# V15_USB_isolator.net
KiCad netlist of a schematic drawn in EAGLE
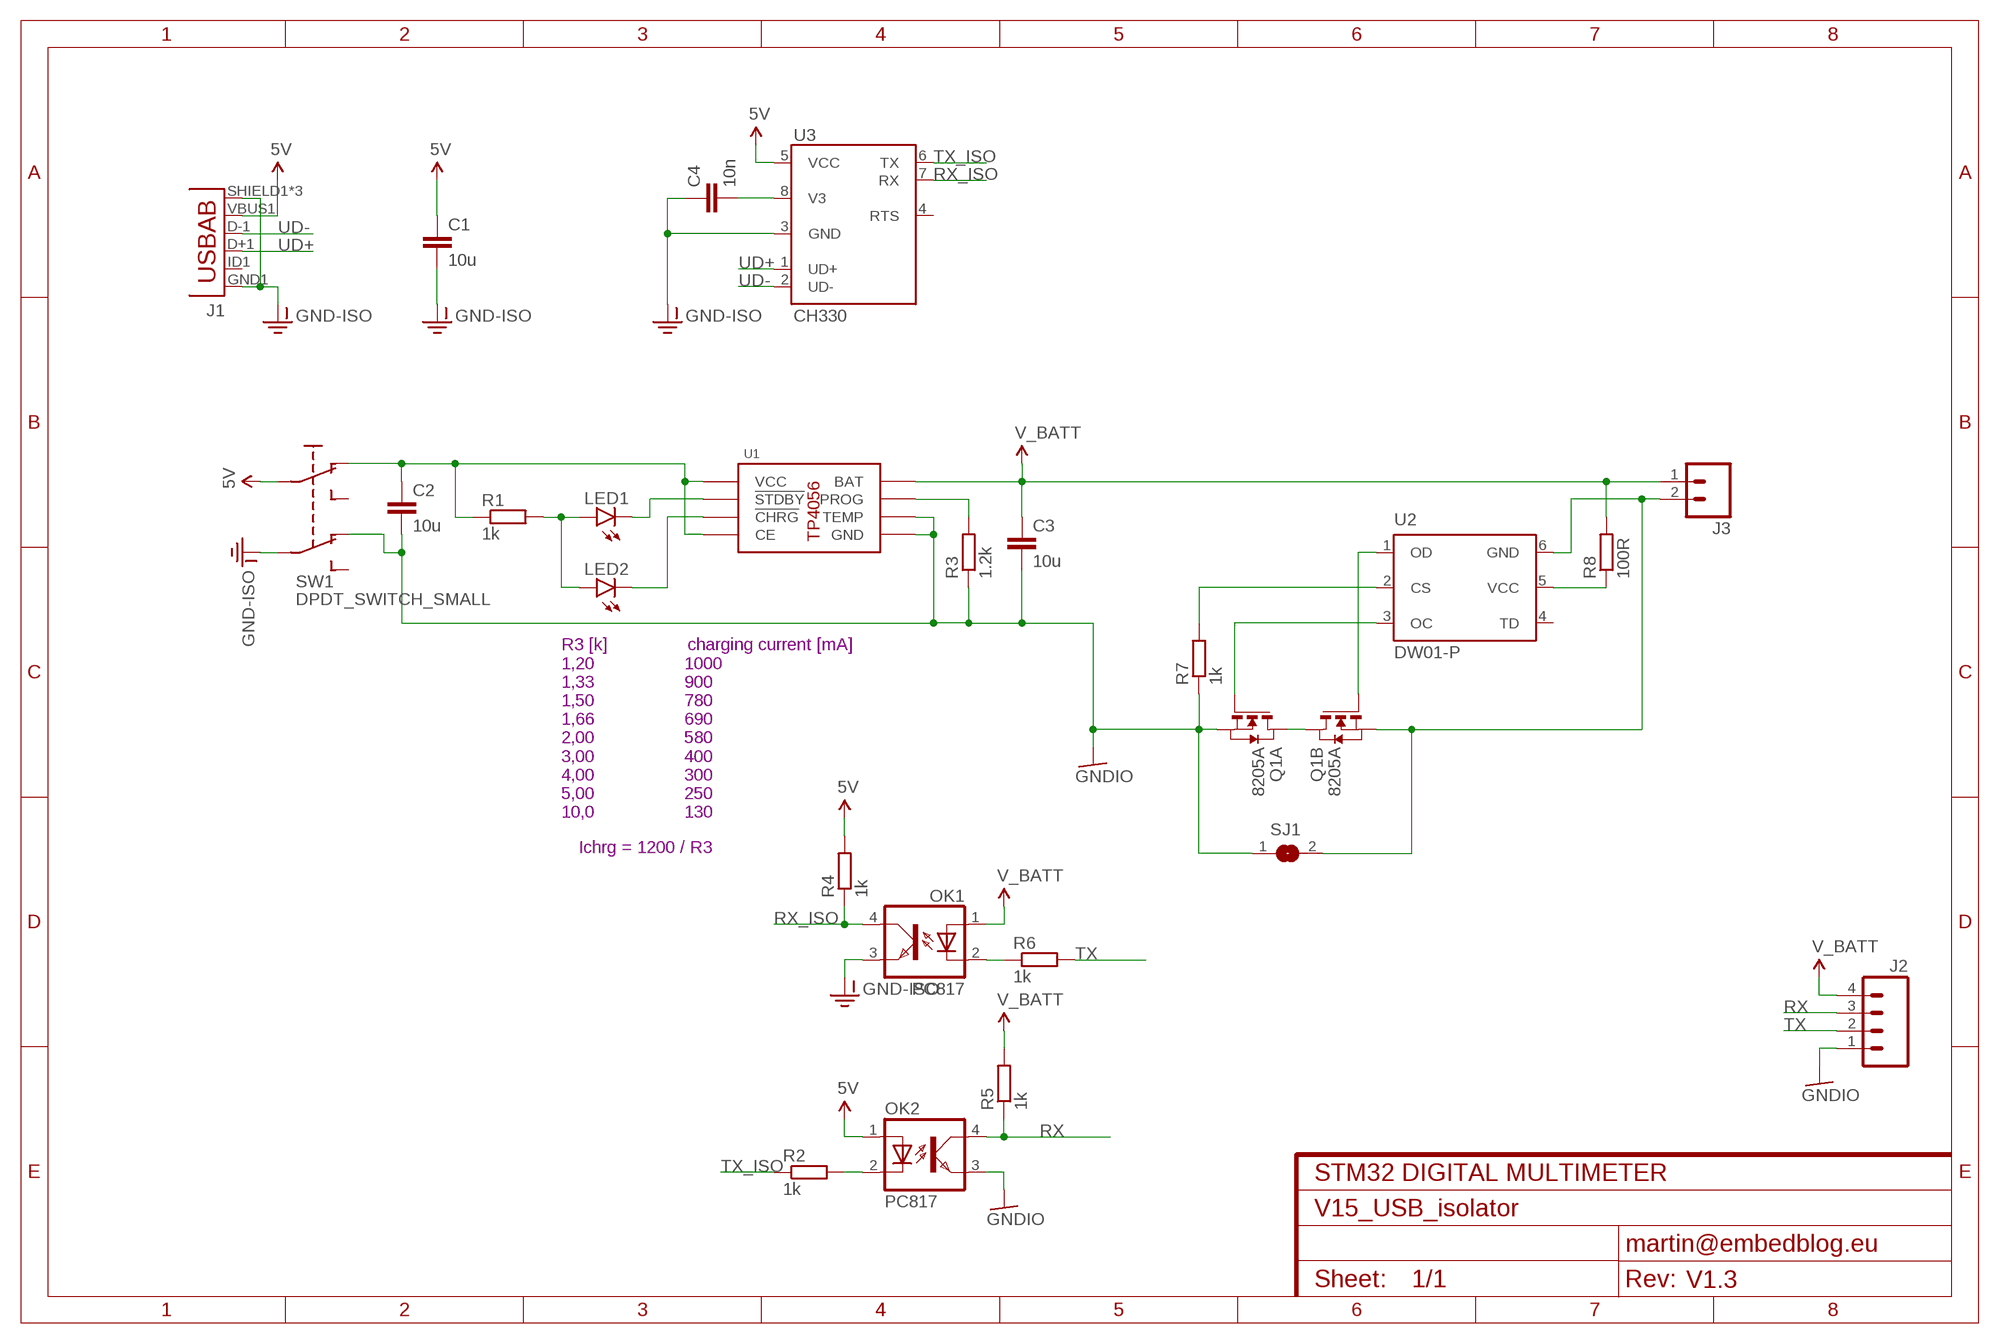
[diagram p0: schematic, sheet 1]

(export (version "E")
  (design (tool "Eeschema 10.0.6"))
  (components
    (comp (ref "C1")
      (value "10u")
      (footprint "eagle-import:C1206")
      (libsource (lib "eagle-import") (part "C-EUC1206"))
    )
    (comp (ref "C2")
      (value "10u")
      (footprint "eagle-import:C1206")
      (libsource (lib "eagle-import") (part "C-EUC1206"))
    )
    (comp (ref "C3")
      (value "10u")
      (footprint "eagle-import:C1206")
      (libsource (lib "eagle-import") (part "C-EUC1206"))
    )
    (comp (ref "C4")
      (value "10n")
      (footprint "eagle-import:C1206")
      (libsource (lib "eagle-import") (part "C-EUC1206"))
    )
    (comp (ref "J1")
      (value "USB-ABCONN-11794")
      (footprint "eagle-import:USB-AB-MICRO-SMD_V03")
      (libsource (lib "eagle-import") (part "USB-ABCONN-11794"))
    )
    (comp (ref "J2")
      (value "M04PTH")
      (footprint "eagle-import:1X04@1")
      (libsource (lib "eagle-import") (part "M04PTH"))
    )
    (comp (ref "J3")
      (value "M02PTH3")
      (footprint "eagle-import:1X02_LONGPADS")
      (libsource (lib "eagle-import") (part "M02PTH3"))
    )
    (comp (ref "LED1")
      (value "LED1206-BOTTOM")
      (footprint "eagle-import:LED-1206-BOTTOM")
      (libsource (lib "eagle-import") (part "LED1206-BOTTOM"))
    )
    (comp (ref "LED2")
      (value "LED1206-BOTTOM")
      (footprint "eagle-import:LED-1206-BOTTOM")
      (libsource (lib "eagle-import") (part "LED1206-BOTTOM"))
    )
    (comp (ref "OK1")
      (value "PC817")
      (footprint "eagle-import:DIL04")
      (fields (field (name "MPN") "PC817X4J000F"))
      (libsource (lib "eagle-import") (part "PC817"))
    )
    (comp (ref "OK2")
      (value "PC817")
      (footprint "eagle-import:DIL04")
      (fields (field (name "MPN") "PC817X4J000F"))
      (libsource (lib "eagle-import") (part "PC817"))
    )
    (comp (ref "Q1")
      (value "8205A")
      (footprint "eagle-import:TSSOP8")
      (libsource (lib "eagle-import") (part "8205A"))
    )
    (comp (ref "R1")
      (value "1k")
      (footprint "eagle-import:R1206")
      (libsource (lib "eagle-import") (part "R-EU_R1206"))
    )
    (comp (ref "R2")
      (value "1k")
      (footprint "eagle-import:R1206")
      (libsource (lib "eagle-import") (part "R-EU_R1206"))
    )
    (comp (ref "R3")
      (value "1.2k")
      (footprint "eagle-import:R1206")
      (libsource (lib "eagle-import") (part "R-EU_R1206"))
    )
    (comp (ref "R4")
      (value "1k")
      (footprint "eagle-import:R1206")
      (libsource (lib "eagle-import") (part "R-EU_R1206"))
    )
    (comp (ref "R5")
      (value "1k")
      (footprint "eagle-import:R1206")
      (libsource (lib "eagle-import") (part "R-EU_R1206"))
    )
    (comp (ref "R6")
      (value "1k")
      (footprint "eagle-import:R1206")
      (libsource (lib "eagle-import") (part "R-EU_R1206"))
    )
    (comp (ref "R7")
      (value "1k")
      (footprint "eagle-import:R1206")
      (libsource (lib "eagle-import") (part "R-EU_R1206"))
    )
    (comp (ref "R8")
      (value "100R")
      (footprint "eagle-import:R1206")
      (libsource (lib "eagle-import") (part "R-EU_R1206"))
    )
    (comp (ref "SJ1") (value "SJ") (footprint "eagle-import:SJ") (libsource (lib "eagle-import") (part "SJ")))
    (comp (ref "SW1")
      (value "DPDT_SWITCH_SMALL")
      (footprint "eagle-import:DPDT_SMALL")
      (libsource (lib "eagle-import") (part "DPDT_SWITCH_SMALL"))
    )
    (comp (ref "U1")
      (value "TP4056")
      (footprint "eagle-import:SOP8")
      (libsource (lib "eagle-import") (part "TP4056"))
    )
    (comp (ref "U2")
      (value "DW01-P")
      (footprint "eagle-import:SOT23-6L")
      (libsource (lib "eagle-import") (part "DW01-P"))
    )
    (comp (ref "U3")
      (value "CH330")
      (footprint "eagle-import:SO08")
      (libsource (lib "eagle-import") (part "CH330"))
    )
  )
  (nets
    (net (code "1") (name "/RX") (class "Default")
      (node (ref "J2") (pin "3") (pinfunction "3_3") (pintype "passive"))
      (node (ref "OK2") (pin "4") (pinfunction "COL_4") (pintype "passive"))
      (node (ref "R5") (pin "1") (pinfunction "1_1") (pintype "passive"))
    )
    (net (code "2") (name "/RX_ISO") (class "Default")
      (node (ref "OK1") (pin "4") (pinfunction "COL_4") (pintype "passive"))
      (node (ref "R4") (pin "1") (pinfunction "1_1") (pintype "passive"))
      (node (ref "U3") (pin "7") (pinfunction "RX_7") (pintype "bidirectional"))
    )
    (net (code "3") (name "/TX") (class "Default")
      (node (ref "J2") (pin "2") (pinfunction "2_2") (pintype "passive"))
      (node (ref "R6") (pin "2") (pinfunction "2_2") (pintype "passive"))
    )
    (net (code "4") (name "/TX_ISO") (class "Default")
      (node (ref "R2") (pin "1") (pinfunction "1_1") (pintype "passive"))
      (node (ref "U3") (pin "6") (pinfunction "TX_6") (pintype "bidirectional"))
    )
    (net (code "5") (name "/UD+") (class "Default")
      (node (ref "J1") (pin "D+1") (pinfunction "D+_D+1") (pintype "bidirectional"))
      (node (ref "U3") (pin "1") (pinfunction "UD+_1") (pintype "bidirectional"))
    )
    (net (code "6") (name "/UD-") (class "Default")
      (node (ref "J1") (pin "D-1") (pinfunction "D-_D-1") (pintype "bidirectional"))
      (node (ref "U3") (pin "2") (pinfunction "UD-_2") (pintype "bidirectional"))
    )
    (net (code "7") (name "5V") (class "Default")
      (node (ref "C1") (pin "1") (pinfunction "1_1") (pintype "passive"))
      (node (ref "J1") (pin "VBUS1") (pinfunction "VBUS_VBUS1") (pintype "bidirectional"))
      (node (ref "OK2") (pin "1") (pinfunction "A_1") (pintype "passive"))
      (node (ref "R4") (pin "2") (pinfunction "2_2") (pintype "passive"))
      (node (ref "SW1") (pin "P$2") (pinfunction "I1_P$2") (pintype "passive"))
      (node (ref "U3") (pin "5") (pinfunction "VCC_5") (pintype "bidirectional"))
    )
    (net (code "8") (name "GND-ISO") (class "Default")
      (node (ref "C1") (pin "2") (pinfunction "2_2") (pintype "passive"))
      (node (ref "C4") (pin "1") (pinfunction "1_1") (pintype "passive"))
      (node (ref "J1") (pin "GND1") (pinfunction "GND_GND1") (pintype "bidirectional"))
      (node (ref "J1") (pin "SHIELD1") (pinfunction "SHIELD_SHIELD1") (pintype "bidirectional"))
      (node (ref "J1") (pin "SHIELD2") (pinfunction "SHIELD_SHIELD2") (pintype "bidirectional"))
      (node (ref "J1") (pin "SHIELD3") (pinfunction "SHIELD_SHIELD3") (pintype "bidirectional"))
      (node (ref "OK1") (pin "3") (pinfunction "EMIT_3") (pintype "passive"))
      (node (ref "SW1") (pin "P$5") (pinfunction "I2_P$5") (pintype "passive"))
      (node (ref "U3") (pin "3") (pinfunction "GND_3") (pintype "bidirectional"))
    )
    (net (code "9") (name "GNDIO") (class "Default")
      (node (ref "C2") (pin "2") (pinfunction "2_2") (pintype "passive"))
      (node (ref "C3") (pin "2") (pinfunction "2_2") (pintype "passive"))
      (node (ref "J2") (pin "1") (pinfunction "1_1") (pintype "passive"))
      (node (ref "OK2") (pin "3") (pinfunction "EMIT_3") (pintype "passive"))
      (node (ref "Q1") (pin "2") (pinfunction "S_2") (pintype "passive"))
      (node (ref "Q1") (pin "3") (pinfunction "S_3") (pintype "passive"))
      (node (ref "R3") (pin "1") (pinfunction "1_1") (pintype "passive"))
      (node (ref "R7") (pin "1") (pinfunction "1_1") (pintype "passive"))
      (node (ref "SJ1") (pin "1") (pinfunction "1_1") (pintype "passive"))
      (node (ref "SW1") (pin "P$6") (pinfunction "NC2_P$6") (pintype "passive"))
      (node (ref "U1") (pin "1") (pinfunction "TEMP_1") (pintype "bidirectional"))
      (node (ref "U1") (pin "3") (pinfunction "GND_3") (pintype "bidirectional"))
    )
    (net (code "10") (name "Net-(LED1-PadA)") (class "Default")
      (node (ref "LED1") (pin "A") (pinfunction "A_A") (pintype "passive"))
      (node (ref "LED2") (pin "A") (pinfunction "A_A") (pintype "passive"))
      (node (ref "R1") (pin "2") (pinfunction "2_2") (pintype "passive"))
    )
    (net (code "11") (name "Net-(OK1-C)") (class "Default")
      (node (ref "OK1") (pin "2") (pinfunction "C_2") (pintype "passive"))
      (node (ref "R6") (pin "1") (pinfunction "1_1") (pintype "passive"))
    )
    (net (code "12") (name "Net-(OK2-C)") (class "Default")
      (node (ref "OK2") (pin "2") (pinfunction "C_2") (pintype "passive"))
      (node (ref "R2") (pin "2") (pinfunction "2_2") (pintype "passive"))
    )
    (net (code "13") (name "Net-(Q1A-D)") (class "Default")
      (node (ref "Q1") (pin "1") (pinfunction "D_1") (pintype "passive"))
      (node (ref "Q1") (pin "8") (pinfunction "D_8") (pintype "passive"))
    )
    (net (code "14") (name "Net-(Q1A-G)") (class "Default")
      (node (ref "Q1") (pin "4") (pinfunction "G_4") (pintype "passive"))
      (node (ref "U2") (pin "3") (pinfunction "OC_3") (pintype "power_in"))
    )
    (net (code "15") (name "Net-(Q1B-G)") (class "Default")
      (node (ref "Q1") (pin "5") (pinfunction "G_5") (pintype "passive"))
      (node (ref "U2") (pin "1") (pinfunction "OD_1") (pintype "power_in"))
    )
    (net (code "16") (name "Net-(SW1-NC1)") (class "Default")
      (node (ref "C2") (pin "1") (pinfunction "1_1") (pintype "passive"))
      (node (ref "R1") (pin "1") (pinfunction "1_1") (pintype "passive"))
      (node (ref "SW1") (pin "P$1") (pinfunction "NC1_P$1") (pintype "passive"))
      (node (ref "U1") (pin "4") (pinfunction "VCC_4") (pintype "bidirectional"))
      (node (ref "U1") (pin "8") (pinfunction "CE_8") (pintype "bidirectional"))
    )
    (net (code "17") (name "Net-(U1-PROG)") (class "Default")
      (node (ref "R3") (pin "2") (pinfunction "2_2") (pintype "passive"))
      (node (ref "U1") (pin "2") (pinfunction "PROG_2") (pintype "bidirectional"))
    )
    (net (code "18") (name "Net-(U1-~{CHRG})") (class "Default")
      (node (ref "LED2") (pin "C") (pinfunction "C_C") (pintype "passive"))
      (node (ref "U1") (pin "7") (pinfunction "~{CHRG}_7") (pintype "bidirectional"))
    )
    (net (code "19") (name "Net-(U1-~{STDBY})") (class "Default")
      (node (ref "LED1") (pin "C") (pinfunction "C_C") (pintype "passive"))
      (node (ref "U1") (pin "6") (pinfunction "~{STDBY}_6") (pintype "bidirectional"))
    )
    (net (code "20") (name "Net-(U2-CS)") (class "Default")
      (node (ref "R7") (pin "2") (pinfunction "2_2") (pintype "passive"))
      (node (ref "U2") (pin "2") (pinfunction "CS_2") (pintype "input"))
    )
    (net (code "21") (name "Net-(U2-GND)") (class "Default")
      (node (ref "J3") (pin "2") (pinfunction "2_2") (pintype "passive"))
      (node (ref "Q1") (pin "6") (pinfunction "S_6") (pintype "passive"))
      (node (ref "Q1") (pin "7") (pinfunction "S_7") (pintype "passive"))
      (node (ref "SJ1") (pin "2") (pinfunction "2_2") (pintype "passive"))
      (node (ref "U2") (pin "6") (pinfunction "GND_6") (pintype "output"))
    )
    (net (code "22") (name "Net-(U2-VCC)") (class "Default")
      (node (ref "R8") (pin "1") (pinfunction "1_1") (pintype "passive"))
      (node (ref "U2") (pin "5") (pinfunction "VCC_5") (pintype "input"))
    )
    (net (code "23") (name "Net-(U3-V3)") (class "Default")
      (node (ref "C4") (pin "2") (pinfunction "2_2") (pintype "passive"))
      (node (ref "U3") (pin "8") (pinfunction "V3_8") (pintype "bidirectional"))
    )
    (net (code "24") (name "V_BATT") (class "Default")
      (node (ref "C3") (pin "1") (pinfunction "1_1") (pintype "passive"))
      (node (ref "J2") (pin "4") (pinfunction "4_4") (pintype "passive"))
      (node (ref "J3") (pin "1") (pinfunction "1_1") (pintype "passive"))
      (node (ref "OK1") (pin "1") (pinfunction "A_1") (pintype "passive"))
      (node (ref "R5") (pin "2") (pinfunction "2_2") (pintype "passive"))
      (node (ref "R8") (pin "2") (pinfunction "2_2") (pintype "passive"))
      (node (ref "U1") (pin "5") (pinfunction "BAT_5") (pintype "bidirectional"))
    )
    (net (code "25") (name "unconnected-(J1-USBID-PadID1)") (class "Default")
      (node (ref "J1") (pin "ID1") (pinfunction "USBID_ID1") (pintype "bidirectional"))
    )
    (net (code "26") (name "unconnected-(SW1-NO1-PadP$3)") (class "Default")
      (node (ref "SW1") (pin "P$3") (pinfunction "NO1_P$3") (pintype "passive"))
    )
    (net (code "27") (name "unconnected-(SW1-NO2-PadP$4)") (class "Default")
      (node (ref "SW1") (pin "P$4") (pinfunction "NO2_P$4") (pintype "passive"))
    )
    (net (code "28") (name "unconnected-(U2-TD-Pad4)") (class "Default")
      (node (ref "U2") (pin "4") (pinfunction "TD_4") (pintype "output"))
    )
    (net (code "29") (name "unconnected-(U3-RTS-Pad4)") (class "Default")
      (node (ref "U3") (pin "4") (pinfunction "RTS_4") (pintype "bidirectional"))
    )
  )
)
